# adi-interface_v1.net
KiCad netlist of a schematic drawn in EAGLE
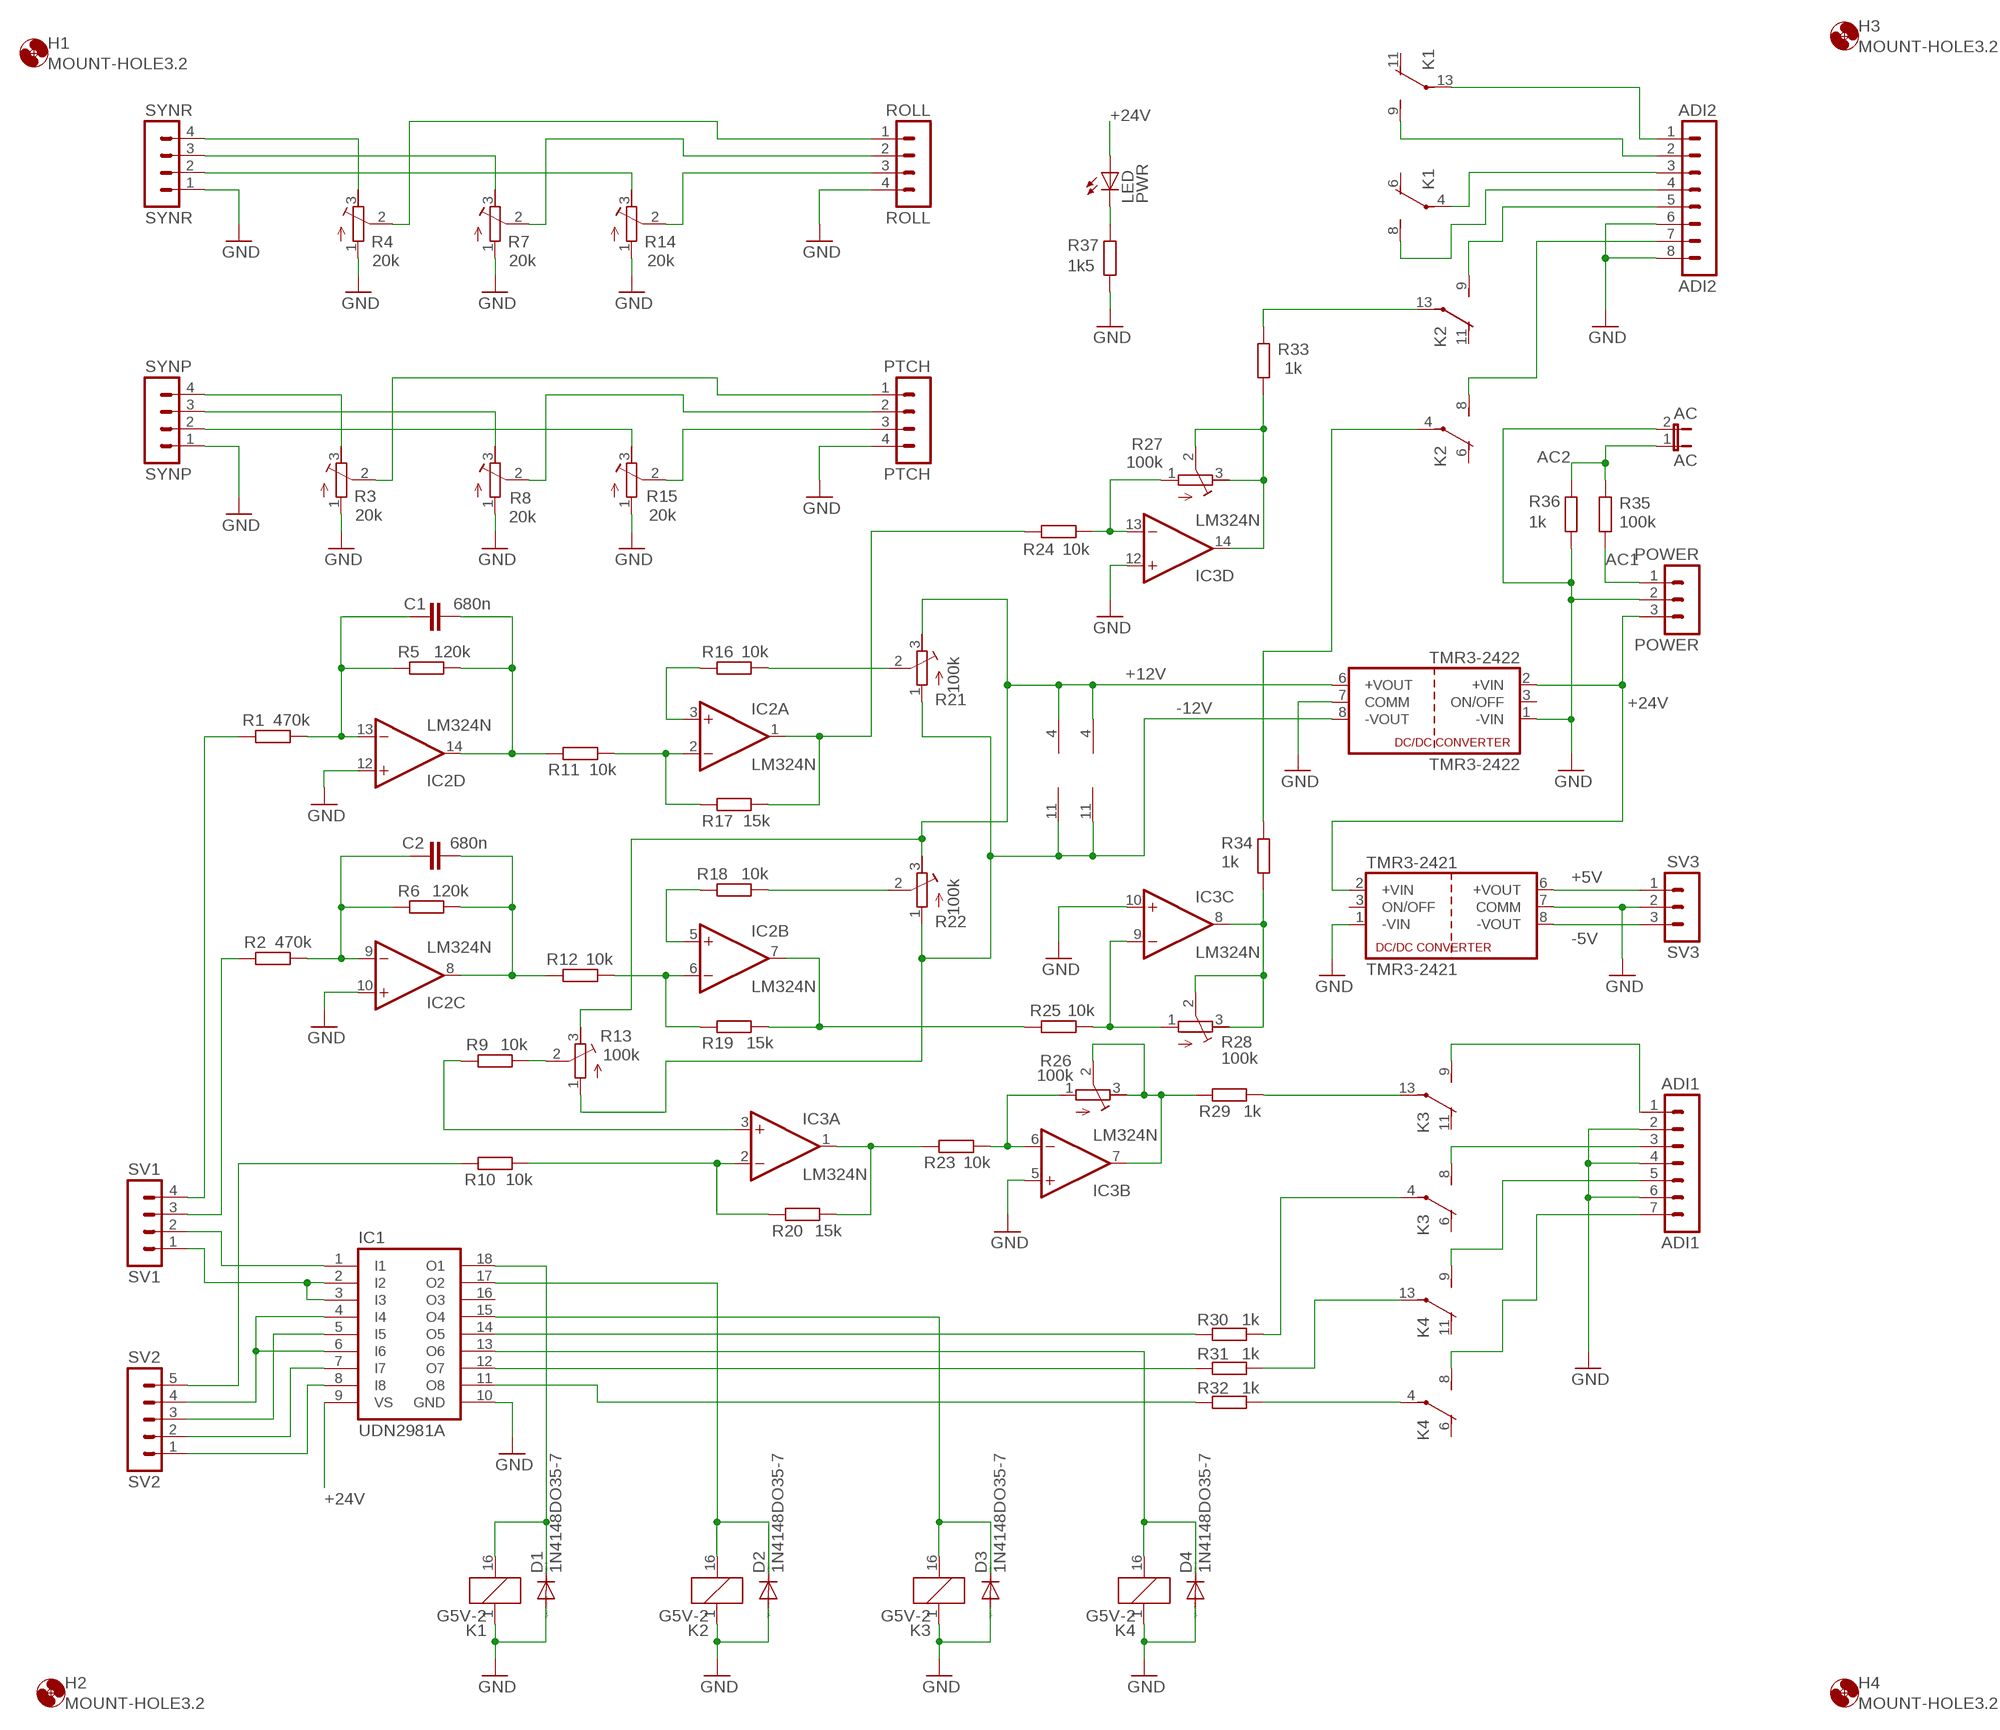
[diagram p0: schematic, sheet 1]

(export (version "E")
  (design (tool "Eeschema 10.0.6"))
  (components
    (comp (ref "AC")
      (value "AC")
      (footprint "eagle-import:1X02")
      (libsource (lib "eagle-import") (part "JUMPER-2PTH"))
    )
    (comp (ref "ADI1")
      (value "ADI1")
      (footprint "eagle-import:MA07-1")
      (libsource (lib "eagle-import") (part "MA07-1"))
    )
    (comp (ref "ADI2")
      (value "ADI2")
      (footprint "eagle-import:MA08-1")
      (libsource (lib "eagle-import") (part "MA08-1"))
    )
    (comp (ref "C1")
      (value "680n")
      (footprint "eagle-import:C050-035X075")
      (libsource (lib "eagle-import") (part "C-EU050-035X075"))
    )
    (comp (ref "C2")
      (value "680n")
      (footprint "eagle-import:C050-035X075")
      (libsource (lib "eagle-import") (part "C-EU050-035X075"))
    )
    (comp (ref "D1")
      (value "1N4148DO35-7")
      (footprint "eagle-import:DO35-7")
      (libsource (lib "eagle-import") (part "1N4148DO35-7"))
    )
    (comp (ref "D2")
      (value "1N4148DO35-7")
      (footprint "eagle-import:DO35-7")
      (libsource (lib "eagle-import") (part "1N4148DO35-7"))
    )
    (comp (ref "D3")
      (value "1N4148DO35-7")
      (footprint "eagle-import:DO35-7")
      (libsource (lib "eagle-import") (part "1N4148DO35-7"))
    )
    (comp (ref "D4")
      (value "1N4148DO35-7")
      (footprint "eagle-import:DO35-7")
      (libsource (lib "eagle-import") (part "1N4148DO35-7"))
    )
    (comp (ref "H1")
      (value "MOUNT-HOLE3.2")
      (footprint "eagle-import:3,2")
      (libsource (lib "eagle-import") (part "MOUNT-HOLE3.2"))
    )
    (comp (ref "H2")
      (value "MOUNT-HOLE3.2")
      (footprint "eagle-import:3,2")
      (libsource (lib "eagle-import") (part "MOUNT-HOLE3.2"))
    )
    (comp (ref "H3")
      (value "MOUNT-HOLE3.2")
      (footprint "eagle-import:3,2")
      (libsource (lib "eagle-import") (part "MOUNT-HOLE3.2"))
    )
    (comp (ref "H4")
      (value "MOUNT-HOLE3.2")
      (footprint "eagle-import:3,2")
      (libsource (lib "eagle-import") (part "MOUNT-HOLE3.2"))
    )
    (comp (ref "IC1")
      (value "UDN2981A")
      (footprint "eagle-import:DIL18")
      (libsource (lib "eagle-import") (part "UDN298A1"))
    )
    (comp (ref "IC2")
      (value "LM324N")
      (footprint "eagle-import:DIL14")
      (libsource (lib "eagle-import") (part "LM324N"))
    )
    (comp (ref "IC3")
      (value "LM324N")
      (footprint "eagle-import:DIL14")
      (libsource (lib "eagle-import") (part "LM324N"))
    )
    (comp (ref "K1")
      (value "G5V-2")
      (footprint "eagle-import:G5V-2")
      (fields (field (name "MPN") "G5V-2 5DC"))
      (libsource (lib "eagle-import") (part "G5V-2"))
    )
    (comp (ref "K2")
      (value "G5V-2")
      (footprint "eagle-import:G5V-2")
      (fields (field (name "MPN") "G5V-2 5DC"))
      (libsource (lib "eagle-import") (part "G5V-2"))
    )
    (comp (ref "K3")
      (value "G5V-2")
      (footprint "eagle-import:G5V-2")
      (fields (field (name "MPN") "G5V-2 5DC"))
      (libsource (lib "eagle-import") (part "G5V-2"))
    )
    (comp (ref "K4")
      (value "G5V-2")
      (footprint "eagle-import:G5V-2")
      (fields (field (name "MPN") "G5V-2 5DC"))
      (libsource (lib "eagle-import") (part "G5V-2"))
    )
    (comp (ref "LED")
      (value "PWR")
      (footprint "eagle-import:LED3MM")
      (libsource (lib "eagle-import") (part "LED3MM"))
    )
    (comp (ref "POWER")
      (value "POWER")
      (footprint "eagle-import:MA03-1")
      (libsource (lib "eagle-import") (part "MA03-1"))
    )
    (comp (ref "PTCH")
      (value "PTCH")
      (footprint "eagle-import:MA04-1")
      (libsource (lib "eagle-import") (part "MA04-1"))
    )
    (comp (ref "R1")
      (value "470k")
      (footprint "eagle-import:0204_7")
      (libsource (lib "eagle-import") (part "R-EU_0204/7"))
    )
    (comp (ref "R2")
      (value "470k")
      (footprint "eagle-import:0204_7")
      (libsource (lib "eagle-import") (part "R-EU_0204/7"))
    )
    (comp (ref "R3")
      (value "20k")
      (footprint "eagle-import:RTRIM64Z")
      (libsource (lib "eagle-import") (part "R-TRIMM64Z"))
    )
    (comp (ref "R4")
      (value "20k")
      (footprint "eagle-import:RTRIM64Z")
      (libsource (lib "eagle-import") (part "R-TRIMM64Z"))
    )
    (comp (ref "R5")
      (value "120k")
      (footprint "eagle-import:0204_7")
      (libsource (lib "eagle-import") (part "R-EU_0204/7"))
    )
    (comp (ref "R6")
      (value "120k")
      (footprint "eagle-import:0204_7")
      (libsource (lib "eagle-import") (part "R-EU_0204/7"))
    )
    (comp (ref "R7")
      (value "20k")
      (footprint "eagle-import:RTRIM64Z")
      (libsource (lib "eagle-import") (part "R-TRIMM64Z"))
    )
    (comp (ref "R8")
      (value "20k")
      (footprint "eagle-import:RTRIM64Z")
      (libsource (lib "eagle-import") (part "R-TRIMM64Z"))
    )
    (comp (ref "R9")
      (value "10k")
      (footprint "eagle-import:0204_7")
      (libsource (lib "eagle-import") (part "R-EU_0204/7"))
    )
    (comp (ref "R10")
      (value "10k")
      (footprint "eagle-import:0204_7")
      (libsource (lib "eagle-import") (part "R-EU_0204/7"))
    )
    (comp (ref "R11")
      (value "10k")
      (footprint "eagle-import:0204_7")
      (libsource (lib "eagle-import") (part "R-EU_0204/7"))
    )
    (comp (ref "R12")
      (value "10k")
      (footprint "eagle-import:0204_7")
      (libsource (lib "eagle-import") (part "R-EU_0204/7"))
    )
    (comp (ref "R13")
      (value "100k")
      (footprint "eagle-import:RTRIM64Z")
      (libsource (lib "eagle-import") (part "R-TRIMM64Z"))
    )
    (comp (ref "R14")
      (value "20k")
      (footprint "eagle-import:RTRIM64Z")
      (libsource (lib "eagle-import") (part "R-TRIMM64Z"))
    )
    (comp (ref "R15")
      (value "20k")
      (footprint "eagle-import:RTRIM64Z")
      (libsource (lib "eagle-import") (part "R-TRIMM64Z"))
    )
    (comp (ref "R16")
      (value "10k")
      (footprint "eagle-import:0204_7")
      (libsource (lib "eagle-import") (part "R-EU_0204/7"))
    )
    (comp (ref "R17")
      (value "15k")
      (footprint "eagle-import:0204_7")
      (libsource (lib "eagle-import") (part "R-EU_0204/7"))
    )
    (comp (ref "R18")
      (value "10k")
      (footprint "eagle-import:0204_7")
      (libsource (lib "eagle-import") (part "R-EU_0204/7"))
    )
    (comp (ref "R19")
      (value "15k")
      (footprint "eagle-import:0204_7")
      (libsource (lib "eagle-import") (part "R-EU_0204/7"))
    )
    (comp (ref "R20")
      (value "15k")
      (footprint "eagle-import:0204_7")
      (libsource (lib "eagle-import") (part "R-EU_0204/7"))
    )
    (comp (ref "R21")
      (value "100k")
      (footprint "eagle-import:RTRIM64Z")
      (libsource (lib "eagle-import") (part "R-TRIMM64Z"))
    )
    (comp (ref "R22")
      (value "100k")
      (footprint "eagle-import:RTRIM64Z")
      (libsource (lib "eagle-import") (part "R-TRIMM64Z"))
    )
    (comp (ref "R23")
      (value "10k")
      (footprint "eagle-import:0204_7")
      (libsource (lib "eagle-import") (part "R-EU_0204/7"))
    )
    (comp (ref "R24")
      (value "10k")
      (footprint "eagle-import:0204_7")
      (libsource (lib "eagle-import") (part "R-EU_0204/7"))
    )
    (comp (ref "R25")
      (value "10k")
      (footprint "eagle-import:0204_7")
      (libsource (lib "eagle-import") (part "R-EU_0204/7"))
    )
    (comp (ref "R26")
      (value "100k")
      (footprint "eagle-import:RTRIM64Z")
      (libsource (lib "eagle-import") (part "R-TRIMM64Z"))
    )
    (comp (ref "R27")
      (value "100k")
      (footprint "eagle-import:RTRIM64Z")
      (libsource (lib "eagle-import") (part "R-TRIMM64Z"))
    )
    (comp (ref "R28")
      (value "100k")
      (footprint "eagle-import:RTRIM64Z")
      (libsource (lib "eagle-import") (part "R-TRIMM64Z"))
    )
    (comp (ref "R29")
      (value "1k")
      (footprint "eagle-import:0204_7")
      (libsource (lib "eagle-import") (part "R-EU_0204/7"))
    )
    (comp (ref "R30")
      (value "1k")
      (footprint "eagle-import:0204_7")
      (libsource (lib "eagle-import") (part "R-EU_0204/7"))
    )
    (comp (ref "R31")
      (value "1k")
      (footprint "eagle-import:0204_7")
      (libsource (lib "eagle-import") (part "R-EU_0204/7"))
    )
    (comp (ref "R32")
      (value "1k")
      (footprint "eagle-import:0204_7")
      (libsource (lib "eagle-import") (part "R-EU_0204/7"))
    )
    (comp (ref "R33")
      (value "1k")
      (footprint "eagle-import:0204_7")
      (libsource (lib "eagle-import") (part "R-EU_0204/7"))
    )
    (comp (ref "R34")
      (value "1k")
      (footprint "eagle-import:0204_7")
      (libsource (lib "eagle-import") (part "R-EU_0204/7"))
    )
    (comp (ref "R35")
      (value "100k")
      (footprint "eagle-import:0204_7")
      (libsource (lib "eagle-import") (part "R-EU_0204/7"))
    )
    (comp (ref "R36")
      (value "1k")
      (footprint "eagle-import:0204_7")
      (libsource (lib "eagle-import") (part "R-EU_0204/7"))
    )
    (comp (ref "R37")
      (value "1k5")
      (footprint "eagle-import:0204_7")
      (libsource (lib "eagle-import") (part "R-EU_0204/7"))
    )
    (comp (ref "ROLL")
      (value "ROLL")
      (footprint "eagle-import:MA04-1")
      (libsource (lib "eagle-import") (part "MA04-1"))
    )
    (comp (ref "SV1")
      (value "SV1")
      (footprint "eagle-import:MA04-1")
      (libsource (lib "eagle-import") (part "MA04-1"))
    )
    (comp (ref "SV2")
      (value "SV2")
      (footprint "eagle-import:MA05-1")
      (libsource (lib "eagle-import") (part "MA05-1"))
    )
    (comp (ref "SV3")
      (value "SV3")
      (footprint "eagle-import:MA03-1")
      (libsource (lib "eagle-import") (part "MA03-1"))
    )
    (comp (ref "SYNP")
      (value "SYNP")
      (footprint "eagle-import:MA04-1")
      (libsource (lib "eagle-import") (part "MA04-1"))
    )
    (comp (ref "SYNR")
      (value "SYNR")
      (footprint "eagle-import:MA04-1")
      (libsource (lib "eagle-import") (part "MA04-1"))
    )
    (comp (ref "TMR3-2421")
      (value "TMR3-2421")
      (footprint "eagle-import:TRACO_SIP-8")
      (libsource (lib "eagle-import") (part "TMR"))
    )
    (comp (ref "TMR3-2422")
      (value "TMR3-2422")
      (footprint "eagle-import:TRACO_SIP-8")
      (libsource (lib "eagle-import") (part "TMR"))
    )
  )
  (nets
    (net (code "1") (name "/+5V") (class "Default")
      (node (ref "SV3") (pin "1") (pinfunction "1_1") (pintype "passive"))
      (node (ref "TMR3-2421") (pin "6") (pinfunction "+VOUT_6") (pintype "passive"))
    )
    (net (code "2") (name "/+12V") (class "Default")
      (node (ref "IC2") (pin "4") (pinfunction "V+_4") (pintype "power_in"))
      (node (ref "IC3") (pin "4") (pinfunction "V+_4") (pintype "power_in"))
      (node (ref "R13") (pin "3") (pinfunction "E_3") (pintype "passive"))
      (node (ref "R21") (pin "3") (pinfunction "E_3") (pintype "passive"))
      (node (ref "R22") (pin "3") (pinfunction "E_3") (pintype "passive"))
      (node (ref "TMR3-2422") (pin "6") (pinfunction "+VOUT_6") (pintype "passive"))
    )
    (net (code "3") (name "/+24V") (class "Default")
      (node (ref "IC1") (pin "9") (pinfunction "VS_9") (pintype "passive"))
      (node (ref "LED") (pin "A") (pinfunction "A_A") (pintype "passive"))
      (node (ref "POWER") (pin "3") (pinfunction "3_3") (pintype "passive"))
      (node (ref "TMR3-2421") (pin "2") (pinfunction "+VIN_2") (pintype "passive"))
      (node (ref "TMR3-2422") (pin "2") (pinfunction "+VIN_2") (pintype "passive"))
    )
    (net (code "4") (name "/-5V") (class "Default")
      (node (ref "SV3") (pin "3") (pinfunction "3_3") (pintype "passive"))
      (node (ref "TMR3-2421") (pin "8") (pinfunction "-VOUT_8") (pintype "passive"))
    )
    (net (code "5") (name "/-12V") (class "Default")
      (node (ref "IC2") (pin "11") (pinfunction "V-_11") (pintype "power_in"))
      (node (ref "IC3") (pin "11") (pinfunction "V-_11") (pintype "power_in"))
      (node (ref "R13") (pin "1") (pinfunction "A_1") (pintype "passive"))
      (node (ref "R21") (pin "1") (pinfunction "A_1") (pintype "passive"))
      (node (ref "R22") (pin "1") (pinfunction "A_1") (pintype "passive"))
      (node (ref "TMR3-2422") (pin "8") (pinfunction "-VOUT_8") (pintype "passive"))
    )
    (net (code "6") (name "/AC1") (class "Default")
      (node (ref "POWER") (pin "1") (pinfunction "1_1") (pintype "passive"))
      (node (ref "R35") (pin "1") (pinfunction "1_1") (pintype "passive"))
    )
    (net (code "7") (name "/AC2") (class "Default")
      (node (ref "AC") (pin "1") (pinfunction "1_1") (pintype "passive"))
      (node (ref "R35") (pin "2") (pinfunction "2_2") (pintype "passive"))
      (node (ref "R36") (pin "2") (pinfunction "2_2") (pintype "passive"))
    )
    (net (code "8") (name "GND") (class "Default")
      (node (ref "AC") (pin "2") (pinfunction "2_2") (pintype "passive"))
      (node (ref "ADI1") (pin "2") (pinfunction "2_2") (pintype "passive"))
      (node (ref "ADI1") (pin "4") (pinfunction "4_4") (pintype "passive"))
      (node (ref "ADI1") (pin "6") (pinfunction "6_6") (pintype "passive"))
      (node (ref "ADI2") (pin "6") (pinfunction "6_6") (pintype "passive"))
      (node (ref "ADI2") (pin "8") (pinfunction "8_8") (pintype "passive"))
      (node (ref "D1") (pin "A") (pinfunction "A_A") (pintype "passive"))
      (node (ref "D2") (pin "A") (pinfunction "A_A") (pintype "passive"))
      (node (ref "D3") (pin "A") (pinfunction "A_A") (pintype "passive"))
      (node (ref "D4") (pin "A") (pinfunction "A_A") (pintype "passive"))
      (node (ref "IC1") (pin "10") (pinfunction "GND_10") (pintype "power_in"))
      (node (ref "IC2") (pin "10") (pinfunction "+IN_10") (pintype "input"))
      (node (ref "IC2") (pin "12") (pinfunction "+IN_12") (pintype "input"))
      (node (ref "IC3") (pin "10") (pinfunction "+IN_10") (pintype "input"))
      (node (ref "IC3") (pin "12") (pinfunction "+IN_12") (pintype "input"))
      (node (ref "IC3") (pin "5") (pinfunction "+IN_5") (pintype "input"))
      (node (ref "K1") (pin "1") (pinfunction "1_1") (pintype "passive"))
      (node (ref "K2") (pin "1") (pinfunction "1_1") (pintype "passive"))
      (node (ref "K3") (pin "1") (pinfunction "1_1") (pintype "passive"))
      (node (ref "K4") (pin "1") (pinfunction "1_1") (pintype "passive"))
      (node (ref "POWER") (pin "2") (pinfunction "2_2") (pintype "passive"))
      (node (ref "PTCH") (pin "4") (pinfunction "4_4") (pintype "passive"))
      (node (ref "R14") (pin "1") (pinfunction "A_1") (pintype "passive"))
      (node (ref "R15") (pin "1") (pinfunction "A_1") (pintype "passive"))
      (node (ref "R3") (pin "1") (pinfunction "A_1") (pintype "passive"))
      (node (ref "R36") (pin "1") (pinfunction "1_1") (pintype "passive"))
      (node (ref "R37") (pin "1") (pinfunction "1_1") (pintype "passive"))
      (node (ref "R4") (pin "1") (pinfunction "A_1") (pintype "passive"))
      (node (ref "R7") (pin "1") (pinfunction "A_1") (pintype "passive"))
      (node (ref "R8") (pin "1") (pinfunction "A_1") (pintype "passive"))
      (node (ref "ROLL") (pin "4") (pinfunction "4_4") (pintype "passive"))
      (node (ref "SV3") (pin "2") (pinfunction "2_2") (pintype "passive"))
      (node (ref "SYNP") (pin "1") (pinfunction "1_1") (pintype "passive"))
      (node (ref "SYNR") (pin "1") (pinfunction "1_1") (pintype "passive"))
      (node (ref "TMR3-2421") (pin "1") (pinfunction "-VIN_1") (pintype "passive"))
      (node (ref "TMR3-2421") (pin "7") (pinfunction "COMM_7") (pintype "passive"))
      (node (ref "TMR3-2422") (pin "1") (pinfunction "-VIN_1") (pintype "passive"))
      (node (ref "TMR3-2422") (pin "7") (pinfunction "COMM_7") (pintype "passive"))
    )
    (net (code "9") (name "Net-(IC1-I1)") (class "Default")
      (node (ref "IC1") (pin "1") (pinfunction "I1_1") (pintype "input"))
      (node (ref "SV1") (pin "2") (pinfunction "2_2") (pintype "passive"))
    )
    (net (code "10") (name "Net-(IC1-I2)") (class "Default")
      (node (ref "IC1") (pin "2") (pinfunction "I2_2") (pintype "input"))
      (node (ref "IC1") (pin "3") (pinfunction "I3_3") (pintype "input"))
      (node (ref "SV1") (pin "1") (pinfunction "1_1") (pintype "passive"))
    )
    (net (code "11") (name "Net-(IC1-I4)") (class "Default")
      (node (ref "IC1") (pin "4") (pinfunction "I4_4") (pintype "input"))
      (node (ref "IC1") (pin "6") (pinfunction "I6_6") (pintype "input"))
      (node (ref "SV2") (pin "4") (pinfunction "4_4") (pintype "passive"))
    )
    (net (code "12") (name "Net-(IC1-I5)") (class "Default")
      (node (ref "IC1") (pin "5") (pinfunction "I5_5") (pintype "input"))
      (node (ref "SV2") (pin "3") (pinfunction "3_3") (pintype "passive"))
    )
    (net (code "13") (name "Net-(IC1-I7)") (class "Default")
      (node (ref "IC1") (pin "7") (pinfunction "I7_7") (pintype "input"))
      (node (ref "SV2") (pin "2") (pinfunction "2_2") (pintype "passive"))
    )
    (net (code "14") (name "Net-(IC1-I8)") (class "Default")
      (node (ref "IC1") (pin "8") (pinfunction "I8_8") (pintype "input"))
      (node (ref "SV2") (pin "1") (pinfunction "1_1") (pintype "passive"))
    )
    (net (code "15") (name "Net-(IC1-O1)") (class "Default")
      (node (ref "D1") (pin "C") (pinfunction "C_C") (pintype "passive"))
      (node (ref "IC1") (pin "18") (pinfunction "O1_18") (pintype "open_collector"))
      (node (ref "K1") (pin "16") (pinfunction "2_16") (pintype "passive"))
    )
    (net (code "16") (name "Net-(IC1-O2)") (class "Default")
      (node (ref "D2") (pin "C") (pinfunction "C_C") (pintype "passive"))
      (node (ref "IC1") (pin "17") (pinfunction "O2_17") (pintype "open_collector"))
      (node (ref "K2") (pin "16") (pinfunction "2_16") (pintype "passive"))
    )
    (net (code "17") (name "Net-(IC1-O4)") (class "Default")
      (node (ref "D3") (pin "C") (pinfunction "C_C") (pintype "passive"))
      (node (ref "IC1") (pin "15") (pinfunction "O4_15") (pintype "open_collector"))
      (node (ref "K3") (pin "16") (pinfunction "2_16") (pintype "passive"))
    )
    (net (code "18") (name "Net-(IC1-O5)") (class "Default")
      (node (ref "IC1") (pin "14") (pinfunction "O5_14") (pintype "open_collector"))
      (node (ref "R30") (pin "1") (pinfunction "1_1") (pintype "passive"))
    )
    (net (code "19") (name "Net-(IC1-O6)") (class "Default")
      (node (ref "D4") (pin "C") (pinfunction "C_C") (pintype "passive"))
      (node (ref "IC1") (pin "13") (pinfunction "O6_13") (pintype "open_collector"))
      (node (ref "K4") (pin "16") (pinfunction "2_16") (pintype "passive"))
    )
    (net (code "20") (name "Net-(IC1-O7)") (class "Default")
      (node (ref "IC1") (pin "12") (pinfunction "O7_12") (pintype "open_collector"))
      (node (ref "R31") (pin "1") (pinfunction "1_1") (pintype "passive"))
    )
    (net (code "21") (name "Net-(IC1-O8)") (class "Default")
      (node (ref "IC1") (pin "11") (pinfunction "O8_11") (pintype "open_collector"))
      (node (ref "R32") (pin "1") (pinfunction "1_1") (pintype "passive"))
    )
    (net (code "22") (name "Net-(IC2A-+IN)") (class "Default")
      (node (ref "IC2") (pin "3") (pinfunction "+IN_3") (pintype "input"))
      (node (ref "R16") (pin "1") (pinfunction "1_1") (pintype "passive"))
    )
    (net (code "23") (name "Net-(IC2A--IN)") (class "Default")
      (node (ref "IC2") (pin "2") (pinfunction "-IN_2") (pintype "input"))
      (node (ref "R11") (pin "2") (pinfunction "2_2") (pintype "passive"))
      (node (ref "R17") (pin "1") (pinfunction "1_1") (pintype "passive"))
    )
    (net (code "24") (name "Net-(IC2A-OUT)") (class "Default")
      (node (ref "IC2") (pin "1") (pinfunction "OUT_1") (pintype "output"))
      (node (ref "R17") (pin "2") (pinfunction "2_2") (pintype "passive"))
      (node (ref "R24") (pin "1") (pinfunction "1_1") (pintype "passive"))
    )
    (net (code "25") (name "Net-(IC2B-+IN)") (class "Default")
      (node (ref "IC2") (pin "5") (pinfunction "+IN_5") (pintype "input"))
      (node (ref "R18") (pin "1") (pinfunction "1_1") (pintype "passive"))
    )
    (net (code "26") (name "Net-(IC2B--IN)") (class "Default")
      (node (ref "IC2") (pin "6") (pinfunction "-IN_6") (pintype "input"))
      (node (ref "R12") (pin "2") (pinfunction "2_2") (pintype "passive"))
      (node (ref "R19") (pin "1") (pinfunction "1_1") (pintype "passive"))
    )
    (net (code "27") (name "Net-(IC2B-OUT)") (class "Default")
      (node (ref "IC2") (pin "7") (pinfunction "OUT_7") (pintype "output"))
      (node (ref "R19") (pin "2") (pinfunction "2_2") (pintype "passive"))
      (node (ref "R25") (pin "1") (pinfunction "1_1") (pintype "passive"))
    )
    (net (code "28") (name "Net-(IC2C--IN)") (class "Default")
      (node (ref "C2") (pin "1") (pinfunction "1_1") (pintype "passive"))
      (node (ref "IC2") (pin "9") (pinfunction "-IN_9") (pintype "input"))
      (node (ref "R2") (pin "2") (pinfunction "2_2") (pintype "passive"))
      (node (ref "R6") (pin "1") (pinfunction "1_1") (pintype "passive"))
    )
    (net (code "29") (name "Net-(IC2C-OUT)") (class "Default")
      (node (ref "C2") (pin "2") (pinfunction "2_2") (pintype "passive"))
      (node (ref "IC2") (pin "8") (pinfunction "OUT_8") (pintype "output"))
      (node (ref "R12") (pin "1") (pinfunction "1_1") (pintype "passive"))
      (node (ref "R6") (pin "2") (pinfunction "2_2") (pintype "passive"))
    )
    (net (code "30") (name "Net-(IC2D--IN)") (class "Default")
      (node (ref "C1") (pin "1") (pinfunction "1_1") (pintype "passive"))
      (node (ref "IC2") (pin "13") (pinfunction "-IN_13") (pintype "input"))
      (node (ref "R1") (pin "2") (pinfunction "2_2") (pintype "passive"))
      (node (ref "R5") (pin "1") (pinfunction "1_1") (pintype "passive"))
    )
    (net (code "31") (name "Net-(IC2D-OUT)") (class "Default")
      (node (ref "C1") (pin "2") (pinfunction "2_2") (pintype "passive"))
      (node (ref "IC2") (pin "14") (pinfunction "OUT_14") (pintype "output"))
      (node (ref "R11") (pin "1") (pinfunction "1_1") (pintype "passive"))
      (node (ref "R5") (pin "2") (pinfunction "2_2") (pintype "passive"))
    )
    (net (code "32") (name "Net-(IC3A-+IN)") (class "Default")
      (node (ref "IC3") (pin "3") (pinfunction "+IN_3") (pintype "input"))
      (node (ref "R9") (pin "1") (pinfunction "1_1") (pintype "passive"))
    )
    (net (code "33") (name "Net-(IC3A--IN)") (class "Default")
      (node (ref "IC3") (pin "2") (pinfunction "-IN_2") (pintype "input"))
      (node (ref "R10") (pin "2") (pinfunction "2_2") (pintype "passive"))
      (node (ref "R20") (pin "1") (pinfunction "1_1") (pintype "passive"))
    )
    (net (code "34") (name "Net-(IC3A-OUT)") (class "Default")
      (node (ref "IC3") (pin "1") (pinfunction "OUT_1") (pintype "output"))
      (node (ref "R20") (pin "2") (pinfunction "2_2") (pintype "passive"))
      (node (ref "R23") (pin "1") (pinfunction "1_1") (pintype "passive"))
    )
    (net (code "35") (name "Net-(IC3B--IN)") (class "Default")
      (node (ref "IC3") (pin "6") (pinfunction "-IN_6") (pintype "input"))
      (node (ref "R23") (pin "2") (pinfunction "2_2") (pintype "passive"))
      (node (ref "R26") (pin "1") (pinfunction "A_1") (pintype "passive"))
    )
    (net (code "36") (name "Net-(IC3B-OUT)") (class "Default")
      (node (ref "IC3") (pin "7") (pinfunction "OUT_7") (pintype "output"))
      (node (ref "R26") (pin "2") (pinfunction "S_2") (pintype "passive"))
      (node (ref "R26") (pin "3") (pinfunction "E_3") (pintype "passive"))
      (node (ref "R29") (pin "1") (pinfunction "1_1") (pintype "passive"))
    )
    (net (code "37") (name "Net-(IC3C--IN)") (class "Default")
      (node (ref "IC3") (pin "9") (pinfunction "-IN_9") (pintype "input"))
      (node (ref "R25") (pin "2") (pinfunction "2_2") (pintype "passive"))
      (node (ref "R28") (pin "1") (pinfunction "A_1") (pintype "passive"))
    )
    (net (code "38") (name "Net-(IC3C-OUT)") (class "Default")
      (node (ref "IC3") (pin "8") (pinfunction "OUT_8") (pintype "output"))
      (node (ref "R28") (pin "2") (pinfunction "S_2") (pintype "passive"))
      (node (ref "R28") (pin "3") (pinfunction "E_3") (pintype "passive"))
      (node (ref "R34") (pin "1") (pinfunction "1_1") (pintype "passive"))
    )
    (net (code "39") (name "Net-(IC3D--IN)") (class "Default")
      (node (ref "IC3") (pin "13") (pinfunction "-IN_13") (pintype "input"))
      (node (ref "R24") (pin "2") (pinfunction "2_2") (pintype "passive"))
      (node (ref "R27") (pin "1") (pinfunction "A_1") (pintype "passive"))
    )
    (net (code "40") (name "Net-(IC3D-OUT)") (class "Default")
      (node (ref "IC3") (pin "14") (pinfunction "OUT_14") (pintype "output"))
      (node (ref "R27") (pin "2") (pinfunction "S_2") (pintype "passive"))
      (node (ref "R27") (pin "3") (pinfunction "E_3") (pintype "passive"))
      (node (ref "R33") (pin "1") (pinfunction "1_1") (pintype "passive"))
    )
    (net (code "41") (name "Net-(K1A-P)") (class "Default")
      (node (ref "ADI2") (pin "3") (pinfunction "3_3") (pintype "passive"))
      (node (ref "K1") (pin "4") (pinfunction "P_4") (pintype "passive"))
    )
    (net (code "42") (name "Net-(K1A-S)") (class "Default")
      (node (ref "ADI2") (pin "4") (pinfunction "4_4") (pintype "passive"))
      (node (ref "K1") (pin "8") (pinfunction "S_8") (pintype "passive"))
    )
    (net (code "43") (name "Net-(K1B-P)") (class "Default")
      (node (ref "ADI2") (pin "1") (pinfunction "1_1") (pintype "passive"))
      (node (ref "K1") (pin "13") (pinfunction "P_13") (pintype "passive"))
    )
    (net (code "44") (name "Net-(K1B-S)") (class "Default")
      (node (ref "ADI2") (pin "2") (pinfunction "2_2") (pintype "passive"))
      (node (ref "K1") (pin "9") (pinfunction "S_9") (pintype "passive"))
    )
    (net (code "45") (name "Net-(K2A-P)") (class "Default")
      (node (ref "K2") (pin "4") (pinfunction "P_4") (pintype "passive"))
      (node (ref "R34") (pin "2") (pinfunction "2_2") (pintype "passive"))
    )
    (net (code "46") (name "Net-(K2A-S)") (class "Default")
      (node (ref "ADI2") (pin "7") (pinfunction "7_7") (pintype "passive"))
      (node (ref "K2") (pin "8") (pinfunction "S_8") (pintype "passive"))
    )
    (net (code "47") (name "Net-(K2B-P)") (class "Default")
      (node (ref "K2") (pin "13") (pinfunction "P_13") (pintype "passive"))
      (node (ref "R33") (pin "2") (pinfunction "2_2") (pintype "passive"))
    )
    (net (code "48") (name "Net-(K2B-S)") (class "Default")
      (node (ref "ADI2") (pin "5") (pinfunction "5_5") (pintype "passive"))
      (node (ref "K2") (pin "9") (pinfunction "S_9") (pintype "passive"))
    )
    (net (code "49") (name "Net-(K3A-P)") (class "Default")
      (node (ref "K3") (pin "4") (pinfunction "P_4") (pintype "passive"))
      (node (ref "R30") (pin "2") (pinfunction "2_2") (pintype "passive"))
    )
    (net (code "50") (name "Net-(K3A-S)") (class "Default")
      (node (ref "ADI1") (pin "3") (pinfunction "3_3") (pintype "passive"))
      (node (ref "K3") (pin "8") (pinfunction "S_8") (pintype "passive"))
    )
    (net (code "51") (name "Net-(K3B-P)") (class "Default")
      (node (ref "K3") (pin "13") (pinfunction "P_13") (pintype "passive"))
      (node (ref "R29") (pin "2") (pinfunction "2_2") (pintype "passive"))
    )
    (net (code "52") (name "Net-(K3B-S)") (class "Default")
      (node (ref "ADI1") (pin "1") (pinfunction "1_1") (pintype "passive"))
      (node (ref "K3") (pin "9") (pinfunction "S_9") (pintype "passive"))
    )
    (net (code "53") (name "Net-(K4A-P)") (class "Default")
      (node (ref "K4") (pin "4") (pinfunction "P_4") (pintype "passive"))
      (node (ref "R32") (pin "2") (pinfunction "2_2") (pintype "passive"))
    )
    (net (code "54") (name "Net-(K4A-S)") (class "Default")
      (node (ref "ADI1") (pin "7") (pinfunction "7_7") (pintype "passive"))
      (node (ref "K4") (pin "8") (pinfunction "S_8") (pintype "passive"))
    )
    (net (code "55") (name "Net-(K4B-P)") (class "Default")
      (node (ref "K4") (pin "13") (pinfunction "P_13") (pintype "passive"))
      (node (ref "R31") (pin "2") (pinfunction "2_2") (pintype "passive"))
    )
    (net (code "56") (name "Net-(K4B-S)") (class "Default")
      (node (ref "ADI1") (pin "5") (pinfunction "5_5") (pintype "passive"))
      (node (ref "K4") (pin "9") (pinfunction "S_9") (pintype "passive"))
    )
    (net (code "57") (name "Net-(LED-C)") (class "Default")
      (node (ref "LED") (pin "K") (pinfunction "C_K") (pintype "passive"))
      (node (ref "R37") (pin "2") (pinfunction "2_2") (pintype "passive"))
    )
    (net (code "58") (name "Net-(R1-Pad1)") (class "Default")
      (node (ref "R1") (pin "1") (pinfunction "1_1") (pintype "passive"))
      (node (ref "SV1") (pin "4") (pinfunction "4_4") (pintype "passive"))
    )
    (net (code "59") (name "Net-(R2-Pad1)") (class "Default")
      (node (ref "R2") (pin "1") (pinfunction "1_1") (pintype "passive"))
      (node (ref "SV1") (pin "3") (pinfunction "3_3") (pintype "passive"))
    )
    (net (code "60") (name "Net-(R3-E)") (class "Default")
      (node (ref "R3") (pin "3") (pinfunction "E_3") (pintype "passive"))
      (node (ref "SYNP") (pin "4") (pinfunction "4_4") (pintype "passive"))
    )
    (net (code "61") (name "Net-(R3-S)") (class "Default")
      (node (ref "PTCH") (pin "1") (pinfunction "1_1") (pintype "passive"))
      (node (ref "R3") (pin "2") (pinfunction "S_2") (pintype "passive"))
    )
    (net (code "62") (name "Net-(R4-E)") (class "Default")
      (node (ref "R4") (pin "3") (pinfunction "E_3") (pintype "passive"))
      (node (ref "SYNR") (pin "4") (pinfunction "4_4") (pintype "passive"))
    )
    (net (code "63") (name "Net-(R4-S)") (class "Default")
      (node (ref "R4") (pin "2") (pinfunction "S_2") (pintype "passive"))
      (node (ref "ROLL") (pin "1") (pinfunction "1_1") (pintype "passive"))
    )
    (net (code "64") (name "Net-(R7-E)") (class "Default")
      (node (ref "R7") (pin "3") (pinfunction "E_3") (pintype "passive"))
      (node (ref "SYNR") (pin "3") (pinfunction "3_3") (pintype "passive"))
    )
    (net (code "65") (name "Net-(R7-S)") (class "Default")
      (node (ref "R7") (pin "2") (pinfunction "S_2") (pintype "passive"))
      (node (ref "ROLL") (pin "2") (pinfunction "2_2") (pintype "passive"))
    )
    (net (code "66") (name "Net-(R8-E)") (class "Default")
      (node (ref "R8") (pin "3") (pinfunction "E_3") (pintype "passive"))
      (node (ref "SYNP") (pin "3") (pinfunction "3_3") (pintype "passive"))
    )
    (net (code "67") (name "Net-(R8-S)") (class "Default")
      (node (ref "PTCH") (pin "2") (pinfunction "2_2") (pintype "passive"))
      (node (ref "R8") (pin "2") (pinfunction "S_2") (pintype "passive"))
    )
    (net (code "68") (name "Net-(R10-Pad1)") (class "Default")
      (node (ref "R10") (pin "1") (pinfunction "1_1") (pintype "passive"))
      (node (ref "SV2") (pin "5") (pinfunction "5_5") (pintype "passive"))
    )
    (net (code "69") (name "Net-(R13-S)") (class "Default")
      (node (ref "R13") (pin "2") (pinfunction "S_2") (pintype "passive"))
      (node (ref "R9") (pin "2") (pinfunction "2_2") (pintype "passive"))
    )
    (net (code "70") (name "Net-(R14-E)") (class "Default")
      (node (ref "R14") (pin "3") (pinfunction "E_3") (pintype "passive"))
      (node (ref "SYNR") (pin "2") (pinfunction "2_2") (pintype "passive"))
    )
    (net (code "71") (name "Net-(R14-S)") (class "Default")
      (node (ref "R14") (pin "2") (pinfunction "S_2") (pintype "passive"))
      (node (ref "ROLL") (pin "3") (pinfunction "3_3") (pintype "passive"))
    )
    (net (code "72") (name "Net-(R15-E)") (class "Default")
      (node (ref "R15") (pin "3") (pinfunction "E_3") (pintype "passive"))
      (node (ref "SYNP") (pin "2") (pinfunction "2_2") (pintype "passive"))
    )
    (net (code "73") (name "Net-(R15-S)") (class "Default")
      (node (ref "PTCH") (pin "3") (pinfunction "3_3") (pintype "passive"))
      (node (ref "R15") (pin "2") (pinfunction "S_2") (pintype "passive"))
    )
    (net (code "74") (name "Net-(R21-S)") (class "Default")
      (node (ref "R16") (pin "2") (pinfunction "2_2") (pintype "passive"))
      (node (ref "R21") (pin "2") (pinfunction "S_2") (pintype "passive"))
    )
    (net (code "75") (name "Net-(R22-S)") (class "Default")
      (node (ref "R18") (pin "2") (pinfunction "2_2") (pintype "passive"))
      (node (ref "R22") (pin "2") (pinfunction "S_2") (pintype "passive"))
    )
    (net (code "76") (name "unconnected-(IC1-O3-Pad16)") (class "Default")
      (node (ref "IC1") (pin "16") (pinfunction "O3_16") (pintype "open_collector"))
    )
    (net (code "77") (name "unconnected-(K1A-O-Pad6)") (class "Default")
      (node (ref "K1") (pin "6") (pinfunction "O_6") (pintype "passive"))
    )
    (net (code "78") (name "unconnected-(K1B-O-Pad11)") (class "Default")
      (node (ref "K1") (pin "11") (pinfunction "O_11") (pintype "passive"))
    )
    (net (code "79") (name "unconnected-(K2A-O-Pad6)") (class "Default")
      (node (ref "K2") (pin "6") (pinfunction "O_6") (pintype "passive"))
    )
    (net (code "80") (name "unconnected-(K2B-O-Pad11)") (class "Default")
      (node (ref "K2") (pin "11") (pinfunction "O_11") (pintype "passive"))
    )
    (net (code "81") (name "unconnected-(K3A-O-Pad6)") (class "Default")
      (node (ref "K3") (pin "6") (pinfunction "O_6") (pintype "passive"))
    )
    (net (code "82") (name "unconnected-(K3B-O-Pad11)") (class "Default")
      (node (ref "K3") (pin "11") (pinfunction "O_11") (pintype "passive"))
    )
    (net (code "83") (name "unconnected-(K4A-O-Pad6)") (class "Default")
      (node (ref "K4") (pin "6") (pinfunction "O_6") (pintype "passive"))
    )
    (net (code "84") (name "unconnected-(K4B-O-Pad11)") (class "Default")
      (node (ref "K4") (pin "11") (pinfunction "O_11") (pintype "passive"))
    )
    (net (code "85") (name "unconnected-(TMR3-2421-ON{slash}OFF-Pad3)") (class "Default")
      (node (ref "TMR3-2421") (pin "3") (pinfunction "ON/OFF_3") (pintype "passive"))
    )
    (net (code "86") (name "unconnected-(TMR3-2422-ON{slash}OFF-Pad3)") (class "Default")
      (node (ref "TMR3-2422") (pin "3") (pinfunction "ON/OFF_3") (pintype "passive"))
    )
  )
)
